# Pcb.net
KiCad netlist of a schematic drawn in Altium Designer
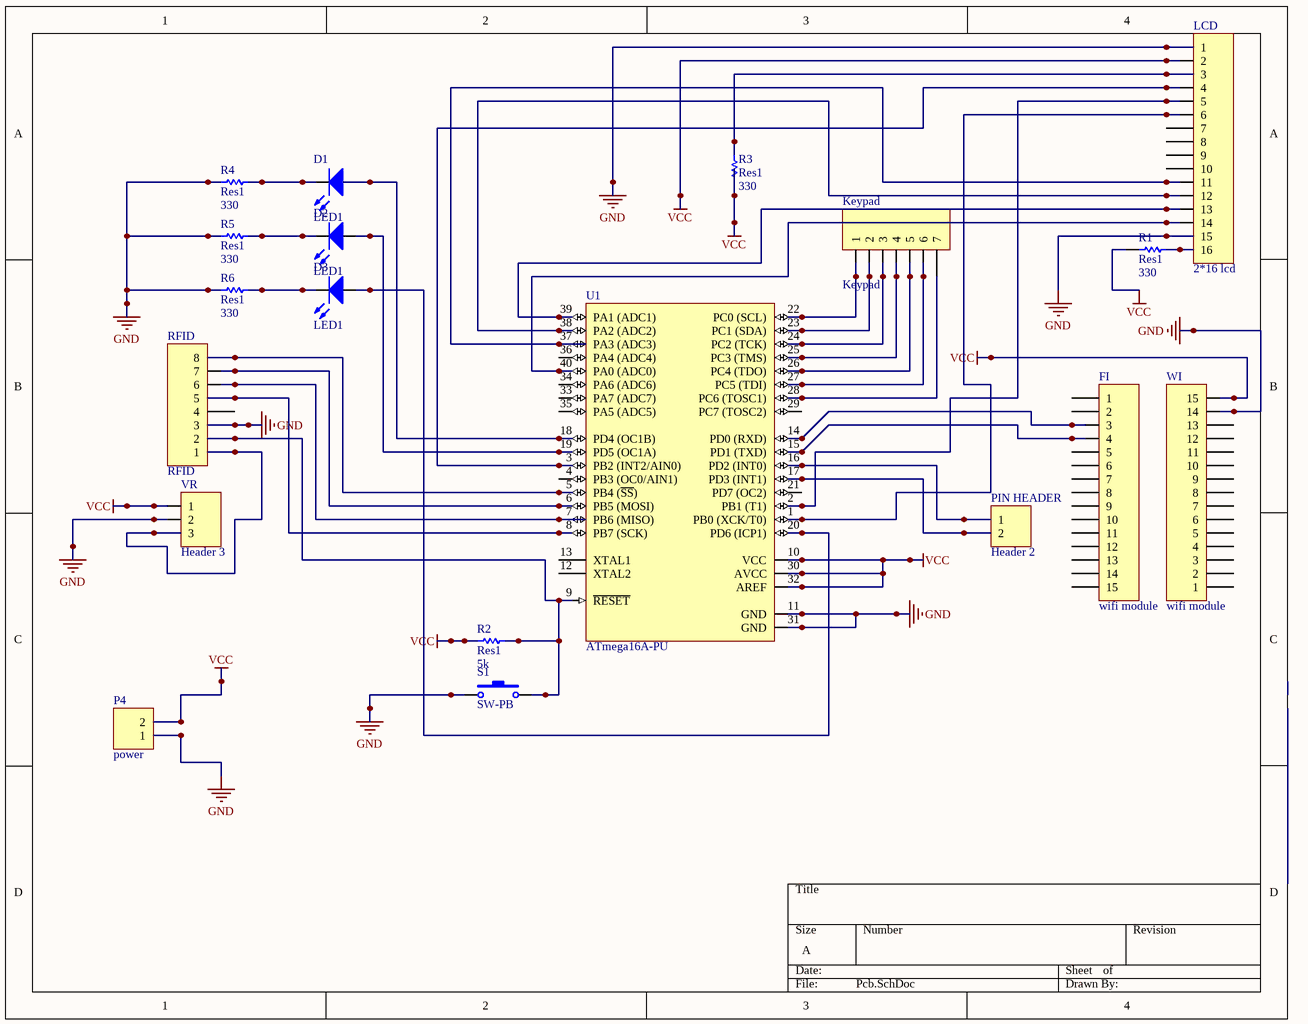
[diagram p0: Pcb.SchDoc]

(export (version "E")
  (design (tool "Eeschema 10.0.6"))
  (components
    (comp (ref "D1")
      (value "LED1")
      (footprint "LED-1")
      (description "Typical RED GaAs LED")
      (fields (field (name "PUBLISHER") "Altium Limited"))
      (libsource (lib "Miscellaneous Devices") (part "LED1"))
    )
    (comp (ref "D2")
      (value "LED1")
      (footprint "LED-1")
      (description "Typical RED GaAs LED")
      (fields (field (name "PUBLISHER") "Altium Limited"))
      (libsource (lib "Miscellaneous Devices") (part "LED1"))
    )
    (comp (ref "D3")
      (value "LED1")
      (footprint "LED-1")
      (description "Typical RED GaAs LED")
      (fields (field (name "PUBLISHER") "Altium Limited"))
      (libsource (lib "Miscellaneous Devices") (part "LED1"))
    )
    (comp (ref "FI")
      (value "wifi module")
      (footprint "HDR1X15")
      (description "Header, 15-Pin")
      (fields (field (name "PUBLISHER") "Altium Limited"))
      (libsource (lib "") (part "Header 15_1"))
    )
    (comp (ref "Keypad")
      (value "Keypad")
      (footprint "HDR1X7")
      (description "Header, 7-Pin")
      (fields (field (name "PUBLISHER") "Altium Limited"))
      (libsource (lib "Miscellaneous Connectors") (part "Header 7"))
    )
    (comp (ref "LCD")
      (value "2*16 lcd")
      (footprint "HDR1X16")
      (description "Header, 16-Pin")
      (fields (field (name "PUBLISHER") "Altium Limited"))
      (libsource (lib "Miscellaneous Connectors") (part "Header 16"))
    )
    (comp (ref "P4")
      (value "power")
      (footprint "HDR1X2")
      (description "Header, 2-Pin")
      (fields (field (name "PUBLISHER") "Altium Limited"))
      (libsource (lib "Miscellaneous Connectors") (part "Header 2"))
    )
    (comp (ref "PIN HEADER")
      (value "Header 2")
      (footprint "HDR1X2")
      (description "Header, 2-Pin")
      (fields (field (name "PUBLISHER") "Altium Limited"))
      (libsource (lib "") (part "Header 2_1"))
    )
    (comp (ref "R1")
      (value "Res1")
      (footprint "AXIAL-0.3")
      (description "Resistor")
      (fields (field (name "ALTIUM_VALUE") "330") (field (name "PUBLISHER") "Altium Limited"))
      (libsource (lib "Miscellaneous Devices") (part "Res1"))
    )
    (comp (ref "R2")
      (value "Res1")
      (footprint "AXIAL-0.3")
      (description "Resistor")
      (fields (field (name "ALTIUM_VALUE") "5k") (field (name "PUBLISHER") "Altium Limited"))
      (libsource (lib "Miscellaneous Devices") (part "Res1"))
    )
    (comp (ref "R3")
      (value "Res1")
      (footprint "AXIAL-0.3")
      (description "Resistor")
      (fields (field (name "ALTIUM_VALUE") "330") (field (name "PUBLISHER") "Altium Limited"))
      (libsource (lib "Miscellaneous Devices") (part "Res1"))
    )
    (comp (ref "R4")
      (value "Res1")
      (footprint "AXIAL-0.3")
      (description "Resistor")
      (fields (field (name "ALTIUM_VALUE") "330") (field (name "PUBLISHER") "Altium Limited"))
      (libsource (lib "Miscellaneous Devices") (part "Res1"))
    )
    (comp (ref "R5")
      (value "Res1")
      (footprint "AXIAL-0.3")
      (description "Resistor")
      (fields (field (name "ALTIUM_VALUE") "330") (field (name "PUBLISHER") "Altium Limited"))
      (libsource (lib "Miscellaneous Devices") (part "Res1"))
    )
    (comp (ref "R6")
      (value "Res1")
      (footprint "AXIAL-0.3")
      (description "Resistor")
      (fields (field (name "ALTIUM_VALUE") "330") (field (name "PUBLISHER") "Altium Limited"))
      (libsource (lib "Miscellaneous Devices") (part "Res1"))
    )
    (comp (ref "RFID")
      (value "RFID")
      (footprint "HDR1X8")
      (description "Header, 8-Pin")
      (fields (field (name "PUBLISHER") "Altium Limited"))
      (libsource (lib "Miscellaneous Connectors") (part "Header 8"))
    )
    (comp (ref "S1")
      (value "SW-PB")
      (footprint "SPST-2")
      (description "Switch")
      (fields (field (name "PUBLISHER") "Altium Limited"))
      (libsource (lib "Miscellaneous Devices") (part "SW-PB"))
    )
    (comp (ref "U1")
      (value "ATmega16A-PU")
      (footprint "40P6")
      (fields (field (name "PUBLISHER") "Altium Limited"))
      (libsource (lib "Atmel Microcontroller 8-Bit megaAVR") (part "ATmega16A-PU"))
    )
    (comp (ref "VR")
      (value "Header 3")
      (footprint "HDR1X3")
      (description "Header, 3-Pin")
      (fields (field (name "PUBLISHER") "Altium Limited"))
      (libsource (lib "Miscellaneous Connectors") (part "Header 3"))
    )
    (comp (ref "WI")
      (value "wifi module")
      (footprint "HDR1X15")
      (description "Header, 15-Pin")
      (fields (field (name "PUBLISHER") "Altium Limited"))
      (libsource (lib "Miscellaneous Connectors") (part "Header 15"))
    )
  )
  (nets
    (net (code "1") (name "GND") (class "Default")
      (node (ref "LCD") (pin "1") (pinfunction "1_1") (pintype "passive"))
      (node (ref "LCD") (pin "15") (pinfunction "15_15") (pintype "passive"))
      (node (ref "P4") (pin "1") (pinfunction "1_1") (pintype "passive"))
      (node (ref "R4") (pin "1") (pinfunction "1_1") (pintype "passive"))
      (node (ref "R5") (pin "1") (pinfunction "1_1") (pintype "passive"))
      (node (ref "R6") (pin "1") (pinfunction "1_1") (pintype "passive"))
      (node (ref "RFID") (pin "3") (pinfunction "3_3") (pintype "passive"))
      (node (ref "S1") (pin "1") (pinfunction "1_1") (pintype "passive"))
      (node (ref "U1") (pin "11") (pinfunction "GND_11") (pintype "power_in"))
      (node (ref "U1") (pin "31") (pinfunction "GND_31") (pintype "power_in"))
      (node (ref "VR") (pin "2") (pinfunction "2_2") (pintype "passive"))
      (node (ref "WI") (pin "14") (pinfunction "14_14") (pintype "passive"))
    )
    (net (code "2") (name "Net-(D1-A)") (class "Default")
      (node (ref "D1") (pin "1") (pinfunction "A_1") (pintype "passive"))
      (node (ref "U1") (pin "18") (pinfunction "PD4_(OC1B)_18") (pintype "bidirectional"))
    )
    (net (code "3") (name "Net-(D1-K)") (class "Default")
      (node (ref "D1") (pin "2") (pinfunction "K_2") (pintype "passive"))
      (node (ref "R4") (pin "2") (pinfunction "2_2") (pintype "passive"))
    )
    (net (code "4") (name "Net-(D2-A)") (class "Default")
      (node (ref "D2") (pin "1") (pinfunction "A_1") (pintype "passive"))
      (node (ref "U1") (pin "19") (pinfunction "PD5_(OC1A)_19") (pintype "bidirectional"))
    )
    (net (code "5") (name "Net-(D2-K)") (class "Default")
      (node (ref "D2") (pin "2") (pinfunction "K_2") (pintype "passive"))
      (node (ref "R5") (pin "2") (pinfunction "2_2") (pintype "passive"))
    )
    (net (code "6") (name "Net-(D3-A)") (class "Default")
      (node (ref "D3") (pin "1") (pinfunction "A_1") (pintype "passive"))
      (node (ref "U1") (pin "20") (pinfunction "PD6_(ICP1)_20") (pintype "bidirectional"))
    )
    (net (code "7") (name "Net-(D3-K)") (class "Default")
      (node (ref "D3") (pin "2") (pinfunction "K_2") (pintype "passive"))
      (node (ref "R6") (pin "2") (pinfunction "2_2") (pintype "passive"))
    )
    (net (code "8") (name "Net-(LCD-Pad3)") (class "Default")
      (node (ref "LCD") (pin "3") (pinfunction "3_3") (pintype "passive"))
      (node (ref "R3") (pin "2") (pinfunction "2_2") (pintype "passive"))
    )
    (net (code "9") (name "Net-(LCD-Pad16)") (class "Default")
      (node (ref "LCD") (pin "16") (pinfunction "16_16") (pintype "passive"))
      (node (ref "R1") (pin "2") (pinfunction "2_2") (pintype "passive"))
    )
    (net (code "10") (name "Net-(RFID-Pad1)") (class "Default")
      (node (ref "RFID") (pin "1") (pinfunction "1_1") (pintype "passive"))
      (node (ref "VR") (pin "3") (pinfunction "3_3") (pintype "passive"))
    )
    (net (code "11") (name "Net-(U1-PA0_(ADC0))") (class "Default")
      (node (ref "LCD") (pin "14") (pinfunction "14_14") (pintype "passive"))
      (node (ref "U1") (pin "40") (pinfunction "PA0_(ADC0)_40") (pintype "bidirectional"))
    )
    (net (code "12") (name "Net-(U1-PA1_(ADC1))") (class "Default")
      (node (ref "LCD") (pin "13") (pinfunction "13_13") (pintype "passive"))
      (node (ref "U1") (pin "39") (pinfunction "PA1_(ADC1)_39") (pintype "bidirectional"))
    )
    (net (code "13") (name "Net-(U1-PA2_(ADC2))") (class "Default")
      (node (ref "LCD") (pin "12") (pinfunction "12_12") (pintype "passive"))
      (node (ref "U1") (pin "38") (pinfunction "PA2_(ADC2)_38") (pintype "bidirectional"))
    )
    (net (code "14") (name "Net-(U1-PA3_(ADC3))") (class "Default")
      (node (ref "LCD") (pin "11") (pinfunction "11_11") (pintype "passive"))
      (node (ref "U1") (pin "37") (pinfunction "PA3_(ADC3)_37") (pintype "bidirectional"))
    )
    (net (code "15") (name "Net-(U1-PB0_(XCK{slash}T0))") (class "Default")
      (node (ref "LCD") (pin "6") (pinfunction "6_6") (pintype "passive"))
      (node (ref "U1") (pin "1") (pinfunction "PB0_(XCK/T0)_1") (pintype "bidirectional"))
    )
    (net (code "16") (name "Net-(U1-PB1_(T1))") (class "Default")
      (node (ref "LCD") (pin "5") (pinfunction "5_5") (pintype "passive"))
      (node (ref "U1") (pin "2") (pinfunction "PB1_(T1)_2") (pintype "bidirectional"))
    )
    (net (code "17") (name "Net-(U1-PB2_(INT2{slash}AIN0))") (class "Default")
      (node (ref "LCD") (pin "4") (pinfunction "4_4") (pintype "passive"))
      (node (ref "U1") (pin "3") (pinfunction "PB2_(INT2/AIN0)_3") (pintype "bidirectional"))
    )
    (net (code "18") (name "Net-(U1-PB4_(~{SS}))") (class "Default")
      (node (ref "RFID") (pin "8") (pinfunction "8_8") (pintype "passive"))
      (node (ref "U1") (pin "5") (pinfunction "PB4_(~{SS})_5") (pintype "bidirectional"))
    )
    (net (code "19") (name "Net-(U1-PB5_(MOSI))") (class "Default")
      (node (ref "RFID") (pin "7") (pinfunction "7_7") (pintype "passive"))
      (node (ref "U1") (pin "6") (pinfunction "PB5_(MOSI)_6") (pintype "bidirectional"))
    )
    (net (code "20") (name "Net-(U1-PB6_(MISO))") (class "Default")
      (node (ref "RFID") (pin "6") (pinfunction "6_6") (pintype "passive"))
      (node (ref "U1") (pin "7") (pinfunction "PB6_(MISO)_7") (pintype "bidirectional"))
    )
    (net (code "21") (name "Net-(U1-PB7_(SCK))") (class "Default")
      (node (ref "RFID") (pin "5") (pinfunction "5_5") (pintype "passive"))
      (node (ref "U1") (pin "8") (pinfunction "PB7_(SCK)_8") (pintype "bidirectional"))
    )
    (net (code "22") (name "Net-(U1-PC0_(SCL))") (class "Default")
      (node (ref "Keypad") (pin "1") (pinfunction "1_1") (pintype "passive"))
      (node (ref "U1") (pin "22") (pinfunction "PC0_(SCL)_22") (pintype "bidirectional"))
    )
    (net (code "23") (name "Net-(U1-PC1_(SDA))") (class "Default")
      (node (ref "Keypad") (pin "2") (pinfunction "2_2") (pintype "passive"))
      (node (ref "U1") (pin "23") (pinfunction "PC1_(SDA)_23") (pintype "bidirectional"))
    )
    (net (code "24") (name "Net-(U1-PC2_(TCK))") (class "Default")
      (node (ref "Keypad") (pin "3") (pinfunction "3_3") (pintype "passive"))
      (node (ref "U1") (pin "24") (pinfunction "PC2_(TCK)_24") (pintype "bidirectional"))
    )
    (net (code "25") (name "Net-(U1-PC3_(TMS))") (class "Default")
      (node (ref "Keypad") (pin "4") (pinfunction "4_4") (pintype "passive"))
      (node (ref "U1") (pin "25") (pinfunction "PC3_(TMS)_25") (pintype "bidirectional"))
    )
    (net (code "26") (name "Net-(U1-PC4_(TDO))") (class "Default")
      (node (ref "Keypad") (pin "5") (pinfunction "5_5") (pintype "passive"))
      (node (ref "U1") (pin "26") (pinfunction "PC4_(TDO)_26") (pintype "bidirectional"))
    )
    (net (code "27") (name "Net-(U1-PC5_(TDI))") (class "Default")
      (node (ref "Keypad") (pin "6") (pinfunction "6_6") (pintype "passive"))
      (node (ref "U1") (pin "27") (pinfunction "PC5_(TDI)_27") (pintype "bidirectional"))
    )
    (net (code "28") (name "Net-(U1-PC6_(TOSC1))") (class "Default")
      (node (ref "Keypad") (pin "7") (pinfunction "7_7") (pintype "passive"))
      (node (ref "U1") (pin "28") (pinfunction "PC6_(TOSC1)_28") (pintype "bidirectional"))
    )
    (net (code "29") (name "Net-(U1-PD0_(RXD))") (class "Default")
      (node (ref "FI") (pin "3") (pinfunction "3_3") (pintype "passive"))
      (node (ref "U1") (pin "14") (pinfunction "PD0_(RXD)_14") (pintype "bidirectional"))
    )
    (net (code "30") (name "Net-(U1-PD1_(TXD))") (class "Default")
      (node (ref "FI") (pin "4") (pinfunction "4_4") (pintype "passive"))
      (node (ref "U1") (pin "15") (pinfunction "PD1_(TXD)_15") (pintype "bidirectional"))
    )
    (net (code "31") (name "Net-(U1-PD2_(INT0))") (class "Default")
      (node (ref "PIN HEADER") (pin "1") (pinfunction "1_1") (pintype "passive"))
      (node (ref "U1") (pin "16") (pinfunction "PD2_(INT0)_16") (pintype "bidirectional"))
    )
    (net (code "32") (name "Net-(U1-PD3_(INT1))") (class "Default")
      (node (ref "PIN HEADER") (pin "2") (pinfunction "2_2") (pintype "passive"))
      (node (ref "U1") (pin "17") (pinfunction "PD3_(INT1)_17") (pintype "bidirectional"))
    )
    (net (code "33") (name "Net-(U1-~{RESET})") (class "Default")
      (node (ref "R2") (pin "1") (pinfunction "1_1") (pintype "passive"))
      (node (ref "RFID") (pin "2") (pinfunction "2_2") (pintype "passive"))
      (node (ref "S1") (pin "2") (pinfunction "2_2") (pintype "passive"))
      (node (ref "U1") (pin "9") (pinfunction "~{RESET}_9") (pintype "input"))
    )
    (net (code "34") (name "VCC") (class "Default")
      (node (ref "LCD") (pin "2") (pinfunction "2_2") (pintype "passive"))
      (node (ref "P4") (pin "2") (pinfunction "2_2") (pintype "passive"))
      (node (ref "R1") (pin "1") (pinfunction "1_1") (pintype "passive"))
      (node (ref "R2") (pin "2") (pinfunction "2_2") (pintype "passive"))
      (node (ref "R3") (pin "1") (pinfunction "1_1") (pintype "passive"))
      (node (ref "U1") (pin "10") (pinfunction "VCC_10") (pintype "power_in"))
      (node (ref "U1") (pin "30") (pinfunction "AVCC_30") (pintype "power_in"))
      (node (ref "U1") (pin "32") (pinfunction "AREF_32") (pintype "power_in"))
      (node (ref "VR") (pin "1") (pinfunction "1_1") (pintype "passive"))
      (node (ref "WI") (pin "15") (pinfunction "15_15") (pintype "passive"))
    )
    (net (code "35") (name "unconnected-(FI-Pad1)") (class "Default")
      (node (ref "FI") (pin "1") (pinfunction "1_1") (pintype "passive"))
    )
    (net (code "36") (name "unconnected-(FI-Pad2)") (class "Default")
      (node (ref "FI") (pin "2") (pinfunction "2_2") (pintype "passive"))
    )
    (net (code "37") (name "unconnected-(FI-Pad5)") (class "Default")
      (node (ref "FI") (pin "5") (pinfunction "5_5") (pintype "passive"))
    )
    (net (code "38") (name "unconnected-(FI-Pad6)") (class "Default")
      (node (ref "FI") (pin "6") (pinfunction "6_6") (pintype "passive"))
    )
    (net (code "39") (name "unconnected-(FI-Pad7)") (class "Default")
      (node (ref "FI") (pin "7") (pinfunction "7_7") (pintype "passive"))
    )
    (net (code "40") (name "unconnected-(FI-Pad8)") (class "Default")
      (node (ref "FI") (pin "8") (pinfunction "8_8") (pintype "passive"))
    )
    (net (code "41") (name "unconnected-(FI-Pad9)") (class "Default")
      (node (ref "FI") (pin "9") (pinfunction "9_9") (pintype "passive"))
    )
    (net (code "42") (name "unconnected-(FI-Pad10)") (class "Default")
      (node (ref "FI") (pin "10") (pinfunction "10_10") (pintype "passive"))
    )
    (net (code "43") (name "unconnected-(FI-Pad11)") (class "Default")
      (node (ref "FI") (pin "11") (pinfunction "11_11") (pintype "passive"))
    )
    (net (code "44") (name "unconnected-(FI-Pad12)") (class "Default")
      (node (ref "FI") (pin "12") (pinfunction "12_12") (pintype "passive"))
    )
    (net (code "45") (name "unconnected-(FI-Pad13)") (class "Default")
      (node (ref "FI") (pin "13") (pinfunction "13_13") (pintype "passive"))
    )
    (net (code "46") (name "unconnected-(FI-Pad14)") (class "Default")
      (node (ref "FI") (pin "14") (pinfunction "14_14") (pintype "passive"))
    )
    (net (code "47") (name "unconnected-(FI-Pad15)") (class "Default")
      (node (ref "FI") (pin "15") (pinfunction "15_15") (pintype "passive"))
    )
    (net (code "48") (name "unconnected-(LCD-Pad7)") (class "Default")
      (node (ref "LCD") (pin "7") (pinfunction "7_7") (pintype "passive"))
    )
    (net (code "49") (name "unconnected-(LCD-Pad8)") (class "Default")
      (node (ref "LCD") (pin "8") (pinfunction "8_8") (pintype "passive"))
    )
    (net (code "50") (name "unconnected-(LCD-Pad9)") (class "Default")
      (node (ref "LCD") (pin "9") (pinfunction "9_9") (pintype "passive"))
    )
    (net (code "51") (name "unconnected-(LCD-Pad10)") (class "Default")
      (node (ref "LCD") (pin "10") (pinfunction "10_10") (pintype "passive"))
    )
    (net (code "52") (name "unconnected-(RFID-Pad4)") (class "Default")
      (node (ref "RFID") (pin "4") (pinfunction "4_4") (pintype "passive"))
    )
    (net (code "53") (name "unconnected-(U1-PA4_(ADC4)-Pad36)") (class "Default")
      (node (ref "U1") (pin "36") (pinfunction "PA4_(ADC4)_36") (pintype "bidirectional"))
    )
    (net (code "54") (name "unconnected-(U1-PA5_(ADC5)-Pad35)") (class "Default")
      (node (ref "U1") (pin "35") (pinfunction "PA5_(ADC5)_35") (pintype "bidirectional"))
    )
    (net (code "55") (name "unconnected-(U1-PA6_(ADC6)-Pad34)") (class "Default")
      (node (ref "U1") (pin "34") (pinfunction "PA6_(ADC6)_34") (pintype "bidirectional"))
    )
    (net (code "56") (name "unconnected-(U1-PA7_(ADC7)-Pad33)") (class "Default")
      (node (ref "U1") (pin "33") (pinfunction "PA7_(ADC7)_33") (pintype "bidirectional"))
    )
    (net (code "57") (name "unconnected-(U1-PB3_(OC0{slash}AIN1)-Pad4)") (class "Default")
      (node (ref "U1") (pin "4") (pinfunction "PB3_(OC0/AIN1)_4") (pintype "bidirectional"))
    )
    (net (code "58") (name "unconnected-(U1-PC7_(TOSC2)-Pad29)") (class "Default")
      (node (ref "U1") (pin "29") (pinfunction "PC7_(TOSC2)_29") (pintype "bidirectional"))
    )
    (net (code "59") (name "unconnected-(U1-PD7_(OC2)-Pad21)") (class "Default")
      (node (ref "U1") (pin "21") (pinfunction "PD7_(OC2)_21") (pintype "bidirectional"))
    )
    (net (code "60") (name "unconnected-(U1-XTAL1-Pad13)") (class "Default")
      (node (ref "U1") (pin "13") (pinfunction "XTAL1_13") (pintype "passive"))
    )
    (net (code "61") (name "unconnected-(U1-XTAL2-Pad12)") (class "Default")
      (node (ref "U1") (pin "12") (pinfunction "XTAL2_12") (pintype "passive"))
    )
    (net (code "62") (name "unconnected-(WI-Pad1)") (class "Default")
      (node (ref "WI") (pin "1") (pinfunction "1_1") (pintype "passive"))
    )
    (net (code "63") (name "unconnected-(WI-Pad2)") (class "Default")
      (node (ref "WI") (pin "2") (pinfunction "2_2") (pintype "passive"))
    )
    (net (code "64") (name "unconnected-(WI-Pad3)") (class "Default")
      (node (ref "WI") (pin "3") (pinfunction "3_3") (pintype "passive"))
    )
    (net (code "65") (name "unconnected-(WI-Pad4)") (class "Default")
      (node (ref "WI") (pin "4") (pinfunction "4_4") (pintype "passive"))
    )
    (net (code "66") (name "unconnected-(WI-Pad5)") (class "Default")
      (node (ref "WI") (pin "5") (pinfunction "5_5") (pintype "passive"))
    )
    (net (code "67") (name "unconnected-(WI-Pad6)") (class "Default")
      (node (ref "WI") (pin "6") (pinfunction "6_6") (pintype "passive"))
    )
    (net (code "68") (name "unconnected-(WI-Pad7)") (class "Default")
      (node (ref "WI") (pin "7") (pinfunction "7_7") (pintype "passive"))
    )
    (net (code "69") (name "unconnected-(WI-Pad8)") (class "Default")
      (node (ref "WI") (pin "8") (pinfunction "8_8") (pintype "passive"))
    )
    (net (code "70") (name "unconnected-(WI-Pad9)") (class "Default")
      (node (ref "WI") (pin "9") (pinfunction "9_9") (pintype "passive"))
    )
    (net (code "71") (name "unconnected-(WI-Pad10)") (class "Default")
      (node (ref "WI") (pin "10") (pinfunction "10_10") (pintype "passive"))
    )
    (net (code "72") (name "unconnected-(WI-Pad11)") (class "Default")
      (node (ref "WI") (pin "11") (pinfunction "11_11") (pintype "passive"))
    )
    (net (code "73") (name "unconnected-(WI-Pad12)") (class "Default")
      (node (ref "WI") (pin "12") (pinfunction "12_12") (pintype "passive"))
    )
    (net (code "74") (name "unconnected-(WI-Pad13)") (class "Default")
      (node (ref "WI") (pin "13") (pinfunction "13_13") (pintype "passive"))
    )
  )
)
